# Sheet1.net
KiCad netlist of a schematic drawn in Altium Designer
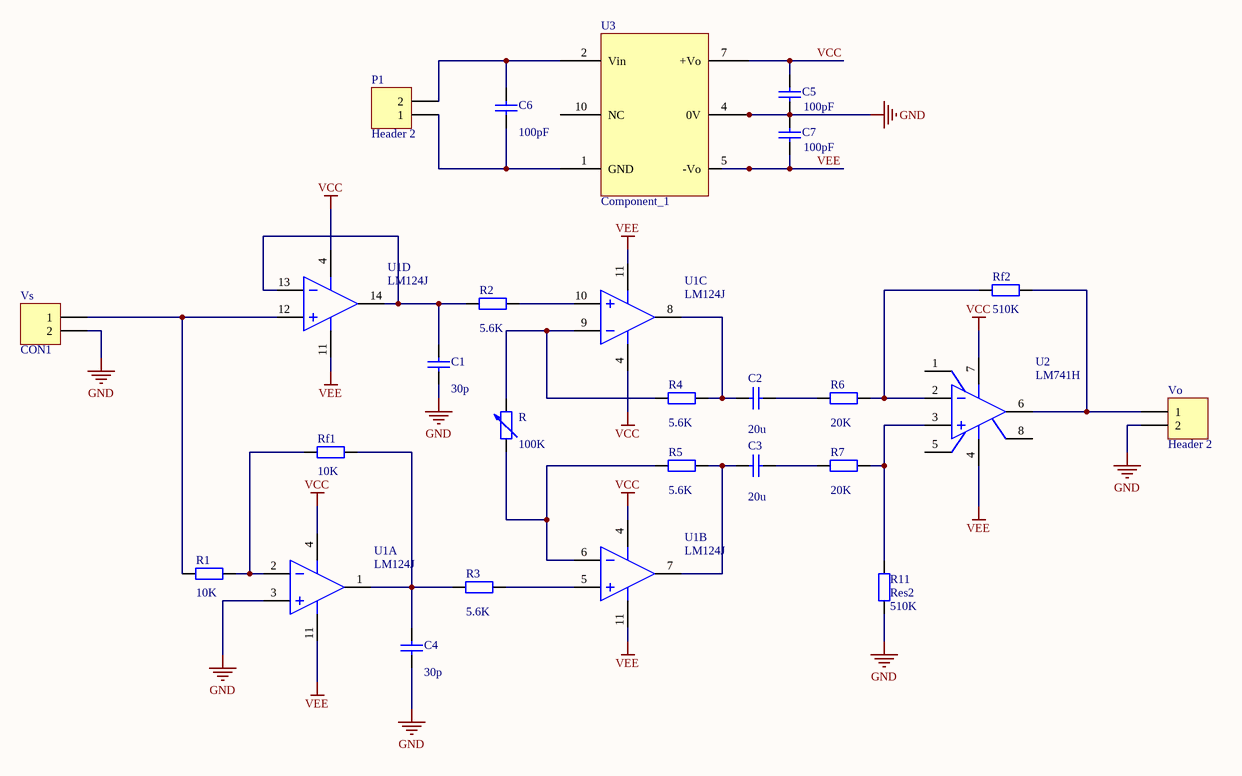
[diagram p0: Sheet1.SchDoc]

(export (version "E")
  (design (tool "Eeschema 10.0.6"))
  (components
    (comp (ref "C1")
      (value "30p")
      (footprint "RAD-0.3")
      (description "Capacitor")
      (fields (field (name "Comment") "Cap") (field (name "PUBLISHER") "Altium Limited"))
      (libsource (lib "Miscellaneous Devices") (part "Cap"))
    )
    (comp (ref "C2")
      (value "20u")
      (footprint "RAD-0.3")
      (description "Capacitor")
      (fields (field (name "Comment") "Cap") (field (name "PUBLISHER") "Altium Limited"))
      (libsource (lib "Miscellaneous Devices") (part "Cap"))
    )
    (comp (ref "C3")
      (value "20u")
      (footprint "RAD-0.3")
      (description "Capacitor")
      (fields (field (name "Comment") "Cap") (field (name "PUBLISHER") "Altium Limited"))
      (libsource (lib "Miscellaneous Devices") (part "Cap"))
    )
    (comp (ref "C4")
      (value "30p")
      (footprint "RAD-0.3")
      (description "Capacitor")
      (fields (field (name "Comment") "Cap") (field (name "PUBLISHER") "Altium Limited"))
      (libsource (lib "Miscellaneous Devices") (part "Cap"))
    )
    (comp (ref "C5")
      (value "100pF")
      (footprint "RAD-0.3")
      (description "Capacitor")
      (fields (field (name "Comment") "Cap") (field (name "PUBLISHER") "Altium Limited"))
      (libsource (lib "Miscellaneous Devices") (part "Cap"))
    )
    (comp (ref "C6")
      (value "100pF")
      (footprint "RAD-0.3")
      (description "Capacitor")
      (fields (field (name "Comment") "Cap") (field (name "PUBLISHER") "Altium Limited"))
      (libsource (lib "Miscellaneous Devices") (part "Cap"))
    )
    (comp (ref "C7")
      (value "100pF")
      (footprint "RAD-0.3")
      (description "Capacitor")
      (fields (field (name "Comment") "Cap") (field (name "PUBLISHER") "Altium Limited"))
      (libsource (lib "Miscellaneous Devices") (part "Cap"))
    )
    (comp (ref "P1")
      (value "Header 2")
      (footprint "HDR1X2")
      (description "Header, 2-Pin")
      (fields (field (name "PUBLISHER") "Altium Limited"))
      (libsource (lib "Miscellaneous Connectors") (part "Header 2"))
    )
    (comp (ref "R")
      (value "100K")
      (footprint "AXIAL-0.6")
      (description "Variable Resistor")
      (fields (field (name "Comment") "Res Adj2") (field (name "PUBLISHER") "Altium Limited"))
      (libsource (lib "Miscellaneous Devices") (part "Res Adj2"))
    )
    (comp (ref "R1")
      (value "10K")
      (footprint "AXIAL-0.4")
      (description "Resistor")
      (fields (field (name "Comment") "Res2") (field (name "PUBLISHER") "Altium Limited"))
      (libsource (lib "Miscellaneous Devices") (part "Res2"))
    )
    (comp (ref "R2")
      (value "5.6K")
      (footprint "AXIAL-0.4")
      (description "Resistor")
      (fields (field (name "Comment") "Res2") (field (name "PUBLISHER") "Altium Limited"))
      (libsource (lib "Miscellaneous Devices") (part "Res2"))
    )
    (comp (ref "R3")
      (value "5.6K")
      (footprint "AXIAL-0.4")
      (description "Resistor")
      (fields (field (name "Comment") "Res2") (field (name "PUBLISHER") "Altium Limited"))
      (libsource (lib "Miscellaneous Devices") (part "Res2"))
    )
    (comp (ref "R4")
      (value "5.6K")
      (footprint "AXIAL-0.4")
      (description "Resistor")
      (fields (field (name "Comment") "Res2") (field (name "PUBLISHER") "Altium Limited"))
      (libsource (lib "Miscellaneous Devices") (part "Res2"))
    )
    (comp (ref "R5")
      (value "5.6K")
      (footprint "AXIAL-0.4")
      (description "Resistor")
      (fields (field (name "Comment") "Res2") (field (name "PUBLISHER") "Altium Limited"))
      (libsource (lib "Miscellaneous Devices") (part "Res2"))
    )
    (comp (ref "R6")
      (value "20K")
      (footprint "AXIAL-0.4")
      (description "Resistor")
      (fields (field (name "Comment") "Res2") (field (name "PUBLISHER") "Altium Limited"))
      (libsource (lib "Miscellaneous Devices") (part "Res2"))
    )
    (comp (ref "R7")
      (value "20K")
      (footprint "AXIAL-0.4")
      (description "Resistor")
      (fields (field (name "Comment") "Res2") (field (name "PUBLISHER") "Altium Limited"))
      (libsource (lib "Miscellaneous Devices") (part "Res2"))
    )
    (comp (ref "R11")
      (value "Res2")
      (footprint "AXIAL-0.4")
      (description "Resistor")
      (fields (field (name "ALTIUM_VALUE") "510K") (field (name "PUBLISHER") "Altium Limited"))
      (libsource (lib "") (part "Res2_2"))
    )
    (comp (ref "Rf1")
      (value "10K")
      (footprint "AXIAL-0.4")
      (description "Resistor")
      (fields (field (name "Comment") "Res2") (field (name "PUBLISHER") "Altium Limited"))
      (libsource (lib "Miscellaneous Devices") (part "Res2"))
    )
    (comp (ref "Rf2")
      (value "510K")
      (footprint "AXIAL-0.4")
      (description "Resistor")
      (fields (field (name "Comment") "Res2") (field (name "PUBLISHER") "Altium Limited"))
      (libsource (lib "") (part "Res2_1"))
    )
    (comp (ref "U1")
      (value "LM124J")
      (footprint "J14A")
      (description "Low Power Quad Operational Amplifier, 14-pin CerDIP")
      (fields
        (field (name "MANUFACTURER") "National Semiconductor")
        (field (name "PUBLISHER") "Altium Limited")
      )
      (libsource (lib "NSC Amplifier") (part "LM124J"))
    )
    (comp (ref "U2")
      (value "LM741H")
      (footprint "H08C")
      (description "Operational Amplifier, 8-pin TO-99")
      (fields
        (field (name "MANUFACTURER") "National Semiconductor")
        (field (name "PUBLISHER") "Altium Limited")
      )
      (libsource (lib "NSC Amplifier") (part "LM741H"))
    )
    (comp (ref "U3")
      (value "Component_1")
      (footprint "PCBComponent_1")
      (libsource (lib "Schlib1") (part "Component_1"))
    )
    (comp (ref "Vo")
      (value "Header 2")
      (footprint "HDR1X2")
      (description "Header, 2-Pin")
      (fields (field (name "PUBLISHER") "Altium Limited"))
      (libsource (lib "") (part "Header 2_2"))
    )
    (comp (ref "Vs")
      (value "CON1")
      (footprint "HDR1X2")
      (description "Header, 2-Pin")
      (fields (field (name "PUBLISHER") "Altium Limited"))
      (libsource (lib "") (part "Header 2_1"))
    )
  )
  (nets
    (net (code "1") (name "GND") (class "Default")
      (node (ref "C1") (pin "1") (pinfunction "1_1") (pintype "passive"))
      (node (ref "C4") (pin "1") (pinfunction "1_1") (pintype "passive"))
      (node (ref "C5") (pin "1") (pinfunction "1_1") (pintype "passive"))
      (node (ref "C7") (pin "2") (pinfunction "2_2") (pintype "passive"))
      (node (ref "R11") (pin "1") (pinfunction "1_1") (pintype "passive"))
      (node (ref "U1") (pin "3") (pinfunction "IN1+_3") (pintype "passive"))
      (node (ref "U3") (pin "4") (pinfunction "0V_4") (pintype "passive"))
      (node (ref "Vo") (pin "2") (pinfunction "2_2") (pintype "passive"))
      (node (ref "Vs") (pin "2") (pinfunction "2_2") (pintype "passive"))
    )
    (net (code "2") (name "Net-(C2-Pad2)") (class "Default")
      (node (ref "C2") (pin "2") (pinfunction "2_2") (pintype "passive"))
      (node (ref "R6") (pin "1") (pinfunction "1_1") (pintype "passive"))
    )
    (net (code "3") (name "Net-(C3-Pad2)") (class "Default")
      (node (ref "C3") (pin "2") (pinfunction "2_2") (pintype "passive"))
      (node (ref "R7") (pin "1") (pinfunction "1_1") (pintype "passive"))
    )
    (net (code "4") (name "Net-(U1A-IN1-)") (class "Default")
      (node (ref "R1") (pin "2") (pinfunction "2_2") (pintype "passive"))
      (node (ref "Rf1") (pin "1") (pinfunction "1_1") (pintype "passive"))
      (node (ref "U1") (pin "2") (pinfunction "IN1-_2") (pintype "passive"))
    )
    (net (code "5") (name "Net-(U1A-OUT1)") (class "Default")
      (node (ref "C4") (pin "2") (pinfunction "2_2") (pintype "passive"))
      (node (ref "R3") (pin "1") (pinfunction "1_1") (pintype "passive"))
      (node (ref "Rf1") (pin "2") (pinfunction "2_2") (pintype "passive"))
      (node (ref "U1") (pin "1") (pinfunction "OUT1_1") (pintype "passive"))
    )
    (net (code "6") (name "Net-(U1B-IN2+)") (class "Default")
      (node (ref "R3") (pin "2") (pinfunction "2_2") (pintype "passive"))
      (node (ref "U1") (pin "5") (pinfunction "IN2+_5") (pintype "input"))
    )
    (net (code "7") (name "Net-(U1B-IN2-)") (class "Default")
      (node (ref "R") (pin "1") (pinfunction "1_1") (pintype "passive"))
      (node (ref "R5") (pin "1") (pinfunction "1_1") (pintype "passive"))
      (node (ref "U1") (pin "6") (pinfunction "IN2-_6") (pintype "input"))
    )
    (net (code "8") (name "Net-(U1B-OUT2)") (class "Default")
      (node (ref "C3") (pin "1") (pinfunction "1_1") (pintype "passive"))
      (node (ref "R5") (pin "2") (pinfunction "2_2") (pintype "passive"))
      (node (ref "U1") (pin "7") (pinfunction "OUT2_7") (pintype "output"))
    )
    (net (code "9") (name "Net-(U1C-IN3+)") (class "Default")
      (node (ref "R2") (pin "2") (pinfunction "2_2") (pintype "passive"))
      (node (ref "U1") (pin "10") (pinfunction "IN3+_10") (pintype "input"))
    )
    (net (code "10") (name "Net-(U1C-IN3-)") (class "Default")
      (node (ref "R") (pin "2") (pinfunction "2_2") (pintype "passive"))
      (node (ref "R4") (pin "1") (pinfunction "1_1") (pintype "passive"))
      (node (ref "U1") (pin "9") (pinfunction "IN3-_9") (pintype "input"))
    )
    (net (code "11") (name "Net-(U1C-OUT3)") (class "Default")
      (node (ref "C2") (pin "1") (pinfunction "1_1") (pintype "passive"))
      (node (ref "R4") (pin "2") (pinfunction "2_2") (pintype "passive"))
      (node (ref "U1") (pin "8") (pinfunction "OUT3_8") (pintype "output"))
    )
    (net (code "12") (name "Net-(U1D-IN4+)") (class "Default")
      (node (ref "R1") (pin "1") (pinfunction "1_1") (pintype "passive"))
      (node (ref "U1") (pin "12") (pinfunction "IN4+_12") (pintype "input"))
      (node (ref "Vs") (pin "1") (pinfunction "1_1") (pintype "passive"))
    )
    (net (code "13") (name "Net-(U1D-IN4-)") (class "Default")
      (node (ref "C1") (pin "2") (pinfunction "2_2") (pintype "passive"))
      (node (ref "R2") (pin "1") (pinfunction "1_1") (pintype "passive"))
      (node (ref "U1") (pin "13") (pinfunction "IN4-_13") (pintype "input"))
      (node (ref "U1") (pin "14") (pinfunction "OUT4_14") (pintype "output"))
    )
    (net (code "14") (name "Net-(U2-IN+)") (class "Default")
      (node (ref "R11") (pin "2") (pinfunction "2_2") (pintype "passive"))
      (node (ref "R7") (pin "2") (pinfunction "2_2") (pintype "passive"))
      (node (ref "U2") (pin "3") (pinfunction "IN+_3") (pintype "passive"))
    )
    (net (code "15") (name "Net-(U2-IN-)") (class "Default")
      (node (ref "R6") (pin "2") (pinfunction "2_2") (pintype "passive"))
      (node (ref "Rf2") (pin "2") (pinfunction "2_2") (pintype "passive"))
      (node (ref "U2") (pin "2") (pinfunction "IN-_2") (pintype "passive"))
    )
    (net (code "16") (name "Net-(U2-OUT)") (class "Default")
      (node (ref "Rf2") (pin "1") (pinfunction "1_1") (pintype "passive"))
      (node (ref "U2") (pin "6") (pinfunction "OUT_6") (pintype "passive"))
      (node (ref "Vo") (pin "1") (pinfunction "1_1") (pintype "passive"))
    )
    (net (code "17") (name "Net-(U3-GND)") (class "Default")
      (node (ref "C6") (pin "1") (pinfunction "1_1") (pintype "passive"))
      (node (ref "P1") (pin "1") (pinfunction "1_1") (pintype "passive"))
      (node (ref "U3") (pin "1") (pinfunction "GND_1") (pintype "power_in"))
    )
    (net (code "18") (name "Net-(U3-Vin)") (class "Default")
      (node (ref "C6") (pin "2") (pinfunction "2_2") (pintype "passive"))
      (node (ref "P1") (pin "2") (pinfunction "2_2") (pintype "passive"))
      (node (ref "U3") (pin "2") (pinfunction "Vin_2") (pintype "power_in"))
    )
    (net (code "19") (name "VCC") (class "Default")
      (node (ref "C5") (pin "2") (pinfunction "2_2") (pintype "passive"))
      (node (ref "U1") (pin "4") (pinfunction "V+_4") (pintype "power_in"))
      (node (ref "U2") (pin "7") (pinfunction "V+_7") (pintype "power_in"))
      (node (ref "U3") (pin "7") (pinfunction "+Vo_7") (pintype "passive"))
    )
    (net (code "20") (name "VEE") (class "Default")
      (node (ref "C7") (pin "1") (pinfunction "1_1") (pintype "passive"))
      (node (ref "U1") (pin "11") (pinfunction "GND_11") (pintype "power_in"))
      (node (ref "U2") (pin "4") (pinfunction "V-_4") (pintype "power_in"))
      (node (ref "U3") (pin "5") (pinfunction "-Vo_5") (pintype "power_in"))
    )
    (net (code "21") (name "unconnected-(U2-NC-Pad8)") (class "Default")
      (node (ref "U2") (pin "8") (pinfunction "NC_8") (pintype "passive"))
    )
    (net (code "22") (name "unconnected-(U2-OFS_NULL-Pad1)") (class "Default")
      (node (ref "U2") (pin "1") (pinfunction "OFS_NULL_1") (pintype "passive"))
    )
    (net (code "23") (name "unconnected-(U2-OFS_NULL-Pad5)") (class "Default")
      (node (ref "U2") (pin "5") (pinfunction "OFS_NULL_5") (pintype "passive"))
    )
    (net (code "24") (name "unconnected-(U3-NC-Pad10)") (class "Default")
      (node (ref "U3") (pin "10") (pinfunction "NC_10") (pintype "passive"))
    )
  )
)
